# UI.net
KiCad netlist of a schematic drawn in EAGLE
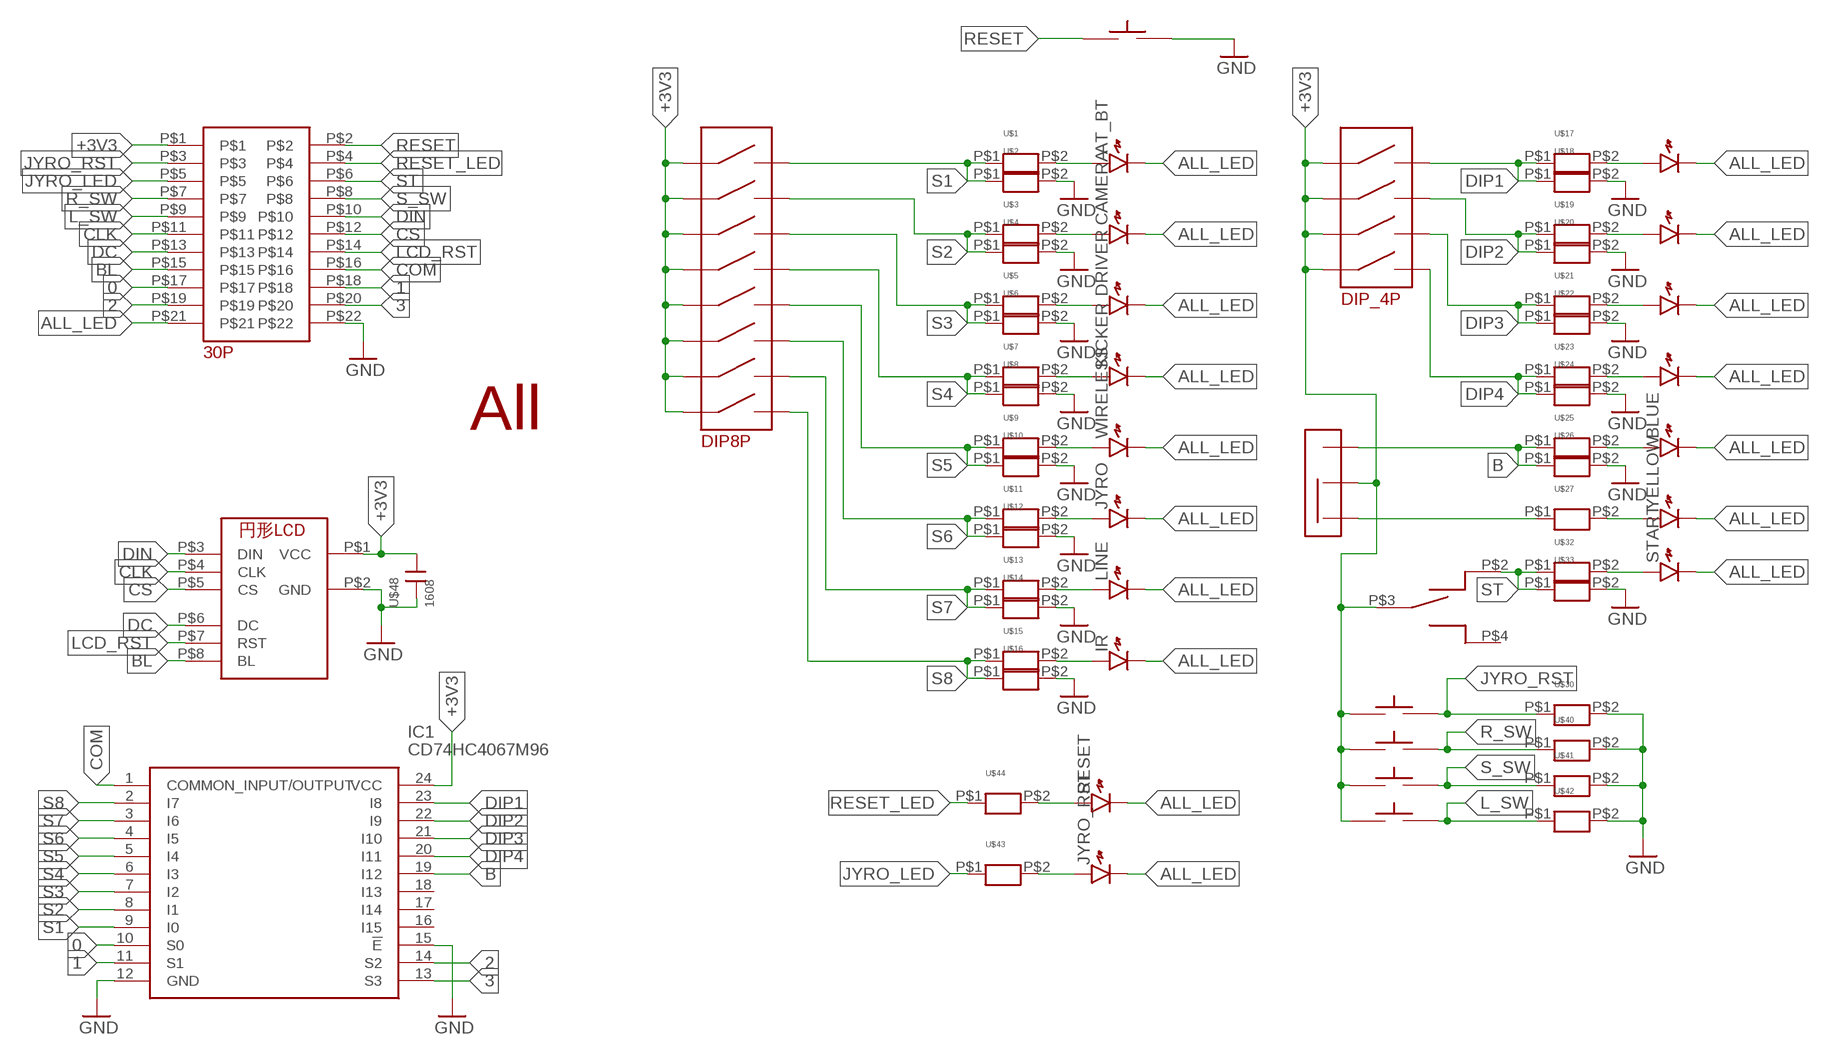
[diagram p0: schematic, sheet 1]
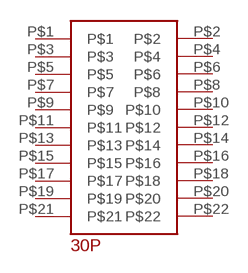
[diagram p1: schematic, sheet 2]

(export (version "E")
  (design (tool "Eeschema 10.0.6"))
  (components
    (comp (ref "AT_BT")
      (value "LED1608")
      (footprint "eagle-import:LED1608")
      (libsource (lib "eagle-import") (part "LED1608"))
    )
    (comp (ref "BLUE")
      (value "LED1608")
      (footprint "eagle-import:LED1608")
      (libsource (lib "eagle-import") (part "LED1608"))
    )
    (comp (ref "CAMERA")
      (value "LED1608")
      (footprint "eagle-import:LED1608")
      (libsource (lib "eagle-import") (part "LED1608"))
    )
    (comp (ref "DRIVER")
      (value "LED1608")
      (footprint "eagle-import:LED1608")
      (libsource (lib "eagle-import") (part "LED1608"))
    )
    (comp (ref "IC1")
      (value "CD74HC4067M96")
      (footprint "eagle-import:SOIC127P1030X265-24N")
      (fields (field (name "MOUSER_PART_NUMBER") "595-CD74HC4067M96"))
      (libsource (lib "eagle-import") (part "CD74HC4067M96"))
    )
    (comp (ref "IR")
      (value "LED1608")
      (footprint "eagle-import:LED1608")
      (libsource (lib "eagle-import") (part "LED1608"))
    )
    (comp (ref "JYRO")
      (value "LED1608")
      (footprint "eagle-import:LED1608")
      (libsource (lib "eagle-import") (part "LED1608"))
    )
    (comp (ref "JYRO_RST")
      (value "LED1608")
      (footprint "eagle-import:LED1608")
      (libsource (lib "eagle-import") (part "LED1608"))
    )
    (comp (ref "KICKER")
      (value "LED1608")
      (footprint "eagle-import:LED1608")
      (libsource (lib "eagle-import") (part "LED1608"))
    )
    (comp (ref "LINE")
      (value "LED1608")
      (footprint "eagle-import:LED1608")
      (libsource (lib "eagle-import") (part "LED1608"))
    )
    (comp (ref "RESET")
      (value "LED1608")
      (footprint "eagle-import:LED1608")
      (libsource (lib "eagle-import") (part "LED1608"))
    )
    (comp (ref "START")
      (value "LED1608")
      (footprint "eagle-import:LED1608")
      (libsource (lib "eagle-import") (part "LED1608"))
    )
    (comp (ref "U$1") (value "R") (footprint "eagle-import:1608") (libsource (lib "eagle-import") (part "R")))
    (comp (ref "U$2") (value "R") (footprint "eagle-import:1608") (libsource (lib "eagle-import") (part "R")))
    (comp (ref "U$3") (value "R") (footprint "eagle-import:1608") (libsource (lib "eagle-import") (part "R")))
    (comp (ref "U$4") (value "R") (footprint "eagle-import:1608") (libsource (lib "eagle-import") (part "R")))
    (comp (ref "U$5") (value "R") (footprint "eagle-import:1608") (libsource (lib "eagle-import") (part "R")))
    (comp (ref "U$6") (value "R") (footprint "eagle-import:1608") (libsource (lib "eagle-import") (part "R")))
    (comp (ref "U$7") (value "R") (footprint "eagle-import:1608") (libsource (lib "eagle-import") (part "R")))
    (comp (ref "U$8") (value "R") (footprint "eagle-import:1608") (libsource (lib "eagle-import") (part "R")))
    (comp (ref "U$9") (value "R") (footprint "eagle-import:1608") (libsource (lib "eagle-import") (part "R")))
    (comp (ref "U$10")
      (value "R")
      (footprint "eagle-import:1608")
      (libsource (lib "eagle-import") (part "R"))
    )
    (comp (ref "U$11")
      (value "R")
      (footprint "eagle-import:1608")
      (libsource (lib "eagle-import") (part "R"))
    )
    (comp (ref "U$12")
      (value "R")
      (footprint "eagle-import:1608")
      (libsource (lib "eagle-import") (part "R"))
    )
    (comp (ref "U$13")
      (value "R")
      (footprint "eagle-import:1608")
      (libsource (lib "eagle-import") (part "R"))
    )
    (comp (ref "U$14")
      (value "R")
      (footprint "eagle-import:1608")
      (libsource (lib "eagle-import") (part "R"))
    )
    (comp (ref "U$15")
      (value "R")
      (footprint "eagle-import:1608")
      (libsource (lib "eagle-import") (part "R"))
    )
    (comp (ref "U$16")
      (value "R")
      (footprint "eagle-import:1608")
      (libsource (lib "eagle-import") (part "R"))
    )
    (comp (ref "U$17")
      (value "R")
      (footprint "eagle-import:1608")
      (libsource (lib "eagle-import") (part "R"))
    )
    (comp (ref "U$18")
      (value "R")
      (footprint "eagle-import:1608")
      (libsource (lib "eagle-import") (part "R"))
    )
    (comp (ref "U$19")
      (value "R")
      (footprint "eagle-import:1608")
      (libsource (lib "eagle-import") (part "R"))
    )
    (comp (ref "U$20")
      (value "R")
      (footprint "eagle-import:1608")
      (libsource (lib "eagle-import") (part "R"))
    )
    (comp (ref "U$21")
      (value "R")
      (footprint "eagle-import:1608")
      (libsource (lib "eagle-import") (part "R"))
    )
    (comp (ref "U$22")
      (value "R")
      (footprint "eagle-import:1608")
      (libsource (lib "eagle-import") (part "R"))
    )
    (comp (ref "U$23")
      (value "R")
      (footprint "eagle-import:1608")
      (libsource (lib "eagle-import") (part "R"))
    )
    (comp (ref "U$24")
      (value "R")
      (footprint "eagle-import:1608")
      (libsource (lib "eagle-import") (part "R"))
    )
    (comp (ref "U$25")
      (value "R")
      (footprint "eagle-import:1608")
      (libsource (lib "eagle-import") (part "R"))
    )
    (comp (ref "U$26")
      (value "R")
      (footprint "eagle-import:1608")
      (libsource (lib "eagle-import") (part "R"))
    )
    (comp (ref "U$27")
      (value "R")
      (footprint "eagle-import:1608")
      (libsource (lib "eagle-import") (part "R"))
    )
    (comp (ref "U$28")
      (value "DIPSW4")
      (footprint "eagle-import:DIPSW4")
      (libsource (lib "eagle-import") (part "DIPSW4"))
    )
    (comp (ref "U$29")
      (value "TAKUTO")
      (footprint "eagle-import:12")
      (libsource (lib "eagle-import") (part "TAKUTO"))
    )
    (comp (ref "U$30")
      (value "R")
      (footprint "eagle-import:1608")
      (libsource (lib "eagle-import") (part "R"))
    )
    (comp (ref "U$31") (value "S") (footprint "eagle-import:S") (libsource (lib "eagle-import") (part "S")))
    (comp (ref "U$32")
      (value "R")
      (footprint "eagle-import:1608")
      (libsource (lib "eagle-import") (part "R"))
    )
    (comp (ref "U$33")
      (value "R")
      (footprint "eagle-import:1608")
      (libsource (lib "eagle-import") (part "R"))
    )
    (comp (ref "U$34")
      (value "TAKUTO")
      (footprint "eagle-import:12")
      (libsource (lib "eagle-import") (part "TAKUTO"))
    )
    (comp (ref "U$35")
      (value "SSW")
      (footprint "eagle-import:SSW")
      (libsource (lib "eagle-import") (part "SSW"))
    )
    (comp (ref "U$36")
      (value "DIPSW8")
      (footprint "eagle-import:DIPSW8")
      (libsource (lib "eagle-import") (part "DIPSW8"))
    )
    (comp (ref "U$37")
      (value "TAKUTO")
      (footprint "eagle-import:12")
      (libsource (lib "eagle-import") (part "TAKUTO"))
    )
    (comp (ref "U$38")
      (value "TAKUTO")
      (footprint "eagle-import:12")
      (libsource (lib "eagle-import") (part "TAKUTO"))
    )
    (comp (ref "U$39")
      (value "TAKUTO")
      (footprint "eagle-import:12")
      (libsource (lib "eagle-import") (part "TAKUTO"))
    )
    (comp (ref "U$40")
      (value "R")
      (footprint "eagle-import:1608")
      (libsource (lib "eagle-import") (part "R"))
    )
    (comp (ref "U$41")
      (value "R")
      (footprint "eagle-import:1608")
      (libsource (lib "eagle-import") (part "R"))
    )
    (comp (ref "U$42")
      (value "R")
      (footprint "eagle-import:1608")
      (libsource (lib "eagle-import") (part "R"))
    )
    (comp (ref "U$43")
      (value "R")
      (footprint "eagle-import:1608")
      (libsource (lib "eagle-import") (part "R"))
    )
    (comp (ref "U$44")
      (value "R")
      (footprint "eagle-import:1608")
      (libsource (lib "eagle-import") (part "R"))
    )
    (comp (ref "U$45")
      (value "LPRP")
      (footprint "eagle-import:LPRO")
      (libsource (lib "eagle-import") (part "LPRP"))
    )
    (comp (ref "U$46")
      (value "LCDEN")
      (footprint "eagle-import:LCD")
      (libsource (lib "eagle-import") (part "LCDEN"))
    )
    (comp (ref "U$48")
      (value "1608")
      (footprint "eagle-import:CON")
      (libsource (lib "eagle-import") (part "1608"))
    )
    (comp (ref "U$49")
      (value "ALL")
      (footprint "eagle-import:ALL")
      (libsource (lib "eagle-import") (part "ALL"))
    )
    (comp (ref "WIRELESS")
      (value "LED1608")
      (footprint "eagle-import:LED1608")
      (libsource (lib "eagle-import") (part "LED1608"))
    )
    (comp (ref "YELLOW")
      (value "LED1608")
      (footprint "eagle-import:LED1608")
      (libsource (lib "eagle-import") (part "LED1608"))
    )
    (comp (ref "Ⅰ")
      (value "LED1608")
      (footprint "eagle-import:LED1608")
      (libsource (lib "eagle-import") (part "LED1608"))
    )
    (comp (ref "Ⅱ")
      (value "LED1608")
      (footprint "eagle-import:LED1608")
      (libsource (lib "eagle-import") (part "LED1608"))
    )
    (comp (ref "Ⅲ")
      (value "LED1608")
      (footprint "eagle-import:LED1608")
      (libsource (lib "eagle-import") (part "LED1608"))
    )
    (comp (ref "Ⅳ")
      (value "LED1608")
      (footprint "eagle-import:LED1608")
      (libsource (lib "eagle-import") (part "LED1608"))
    )
    (comp (ref "U$47")
      (value "LPRP")
      (footprint "eagle-import:LPRO")
      (libsource (lib "eagle-import") (part "LPRP"))
    )
  )
  (nets
    (net (code "1") (name "+3V3") (class "Default")
      (node (ref "IC1") (pin "24") (pinfunction "VCC_24") (pintype "bidirectional"))
      (node (ref "U$28") (pin "P$1") (pinfunction "P$1_P$1") (pintype "bidirectional"))
      (node (ref "U$28") (pin "P$2") (pinfunction "P$2_P$2") (pintype "bidirectional"))
      (node (ref "U$28") (pin "P$3") (pinfunction "P$3_P$3") (pintype "bidirectional"))
      (node (ref "U$28") (pin "P$4") (pinfunction "P$4_P$4") (pintype "bidirectional"))
      (node (ref "U$31") (pin "P$3") (pinfunction "2_P$3") (pintype "bidirectional"))
      (node (ref "U$34") (pin "P$1") (pinfunction "P$1_P$1") (pintype "bidirectional"))
      (node (ref "U$34") (pin "P$2") (pinfunction "P$1_P$2") (pintype "bidirectional"))
      (node (ref "U$35") (pin "P$3") (pinfunction "P$2_P$3") (pintype "bidirectional"))
      (node (ref "U$36") (pin "P$1") (pinfunction "P$1_P$1") (pintype "bidirectional"))
      (node (ref "U$36") (pin "P$2") (pinfunction "P$2_P$2") (pintype "bidirectional"))
      (node (ref "U$36") (pin "P$3") (pinfunction "P$3_P$3") (pintype "bidirectional"))
      (node (ref "U$36") (pin "P$4") (pinfunction "P$4_P$4") (pintype "bidirectional"))
      (node (ref "U$36") (pin "P$5") (pinfunction "P$5_P$5") (pintype "bidirectional"))
      (node (ref "U$36") (pin "P$6") (pinfunction "P$6_P$6") (pintype "bidirectional"))
      (node (ref "U$36") (pin "P$7") (pinfunction "P$7_P$7") (pintype "bidirectional"))
      (node (ref "U$36") (pin "P$8") (pinfunction "P$8_P$8") (pintype "bidirectional"))
      (node (ref "U$37") (pin "P$1") (pinfunction "P$1_P$1") (pintype "bidirectional"))
      (node (ref "U$37") (pin "P$2") (pinfunction "P$1_P$2") (pintype "bidirectional"))
      (node (ref "U$38") (pin "P$1") (pinfunction "P$1_P$1") (pintype "bidirectional"))
      (node (ref "U$38") (pin "P$2") (pinfunction "P$1_P$2") (pintype "bidirectional"))
      (node (ref "U$39") (pin "P$1") (pinfunction "P$1_P$1") (pintype "bidirectional"))
      (node (ref "U$39") (pin "P$2") (pinfunction "P$1_P$2") (pintype "bidirectional"))
      (node (ref "U$45") (pin "P$1") (pinfunction "P$1_P$1") (pintype "bidirectional"))
      (node (ref "U$46") (pin "P$1") (pinfunction "VCC_P$1") (pintype "bidirectional"))
      (node (ref "U$48") (pin "P$1") (pinfunction "1_P$1") (pintype "bidirectional"))
    )
    (net (code "2") (name "0") (class "Default")
      (node (ref "IC1") (pin "10") (pinfunction "S0_10") (pintype "bidirectional"))
      (node (ref "U$45") (pin "P$17") (pinfunction "P$17_P$17") (pintype "bidirectional"))
    )
    (net (code "3") (name "1") (class "Default")
      (node (ref "IC1") (pin "11") (pinfunction "S1_11") (pintype "bidirectional"))
      (node (ref "U$45") (pin "P$18") (pinfunction "P$18_P$18") (pintype "bidirectional"))
    )
    (net (code "4") (name "2") (class "Default")
      (node (ref "IC1") (pin "14") (pinfunction "S2_14") (pintype "bidirectional"))
      (node (ref "U$45") (pin "P$19") (pinfunction "P$19_P$19") (pintype "bidirectional"))
    )
    (net (code "5") (name "3") (class "Default")
      (node (ref "IC1") (pin "13") (pinfunction "S3_13") (pintype "bidirectional"))
      (node (ref "U$45") (pin "P$20") (pinfunction "P$20_P$20") (pintype "bidirectional"))
    )
    (net (code "6") (name "ALL_LED") (class "Default")
      (node (ref "AT_BT") (pin "K") (pinfunction "K_K") (pintype "passive"))
      (node (ref "BLUE") (pin "K") (pinfunction "K_K") (pintype "passive"))
      (node (ref "CAMERA") (pin "K") (pinfunction "K_K") (pintype "passive"))
      (node (ref "DRIVER") (pin "K") (pinfunction "K_K") (pintype "passive"))
      (node (ref "IR") (pin "K") (pinfunction "K_K") (pintype "passive"))
      (node (ref "JYRO") (pin "K") (pinfunction "K_K") (pintype "passive"))
      (node (ref "JYRO_RST") (pin "K") (pinfunction "K_K") (pintype "passive"))
      (node (ref "KICKER") (pin "K") (pinfunction "K_K") (pintype "passive"))
      (node (ref "LINE") (pin "K") (pinfunction "K_K") (pintype "passive"))
      (node (ref "RESET") (pin "K") (pinfunction "K_K") (pintype "passive"))
      (node (ref "START") (pin "K") (pinfunction "K_K") (pintype "passive"))
      (node (ref "U$45") (pin "P$21") (pinfunction "P$21_P$21") (pintype "bidirectional"))
      (node (ref "WIRELESS") (pin "K") (pinfunction "K_K") (pintype "passive"))
      (node (ref "YELLOW") (pin "K") (pinfunction "K_K") (pintype "passive"))
      (node (ref "Ⅰ") (pin "K") (pinfunction "K_K") (pintype "passive"))
      (node (ref "Ⅱ") (pin "K") (pinfunction "K_K") (pintype "passive"))
      (node (ref "Ⅲ") (pin "K") (pinfunction "K_K") (pintype "passive"))
      (node (ref "Ⅳ") (pin "K") (pinfunction "K_K") (pintype "passive"))
    )
    (net (code "7") (name "B") (class "Default")
      (node (ref "IC1") (pin "19") (pinfunction "I12_19") (pintype "bidirectional"))
      (node (ref "U$25") (pin "P$1") (pinfunction "P$1_P$1") (pintype "bidirectional"))
      (node (ref "U$26") (pin "P$1") (pinfunction "P$1_P$1") (pintype "bidirectional"))
      (node (ref "U$35") (pin "P$2") (pinfunction "P$3_P$2") (pintype "bidirectional"))
    )
    (net (code "8") (name "BL") (class "Default")
      (node (ref "U$45") (pin "P$15") (pinfunction "P$15_P$15") (pintype "bidirectional"))
      (node (ref "U$46") (pin "P$8") (pinfunction "BL_P$8") (pintype "bidirectional"))
    )
    (net (code "9") (name "CLK") (class "Default")
      (node (ref "U$45") (pin "P$11") (pinfunction "P$11_P$11") (pintype "bidirectional"))
      (node (ref "U$46") (pin "P$4") (pinfunction "CLK_P$4") (pintype "bidirectional"))
    )
    (net (code "10") (name "COM") (class "Default")
      (node (ref "IC1") (pin "1") (pinfunction "COMMON_INPUT/OUTPUT_1") (pintype "bidirectional"))
      (node (ref "U$45") (pin "P$16") (pinfunction "P$16_P$16") (pintype "bidirectional"))
    )
    (net (code "11") (name "CS") (class "Default")
      (node (ref "U$45") (pin "P$12") (pinfunction "P$12_P$12") (pintype "bidirectional"))
      (node (ref "U$46") (pin "P$5") (pinfunction "CS_P$5") (pintype "bidirectional"))
    )
    (net (code "12") (name "DC") (class "Default")
      (node (ref "U$45") (pin "P$13") (pinfunction "P$13_P$13") (pintype "bidirectional"))
      (node (ref "U$46") (pin "P$6") (pinfunction "DC_P$6") (pintype "bidirectional"))
    )
    (net (code "13") (name "DIN") (class "Default")
      (node (ref "U$45") (pin "P$10") (pinfunction "P$10_P$10") (pintype "bidirectional"))
      (node (ref "U$46") (pin "P$3") (pinfunction "DIN_P$3") (pintype "bidirectional"))
    )
    (net (code "14") (name "DIP1") (class "Default")
      (node (ref "IC1") (pin "23") (pinfunction "I8_23") (pintype "bidirectional"))
      (node (ref "U$17") (pin "P$1") (pinfunction "P$1_P$1") (pintype "bidirectional"))
      (node (ref "U$18") (pin "P$1") (pinfunction "P$1_P$1") (pintype "bidirectional"))
      (node (ref "U$28") (pin "P$8") (pinfunction "P$8_P$8") (pintype "bidirectional"))
    )
    (net (code "15") (name "DIP2") (class "Default")
      (node (ref "IC1") (pin "22") (pinfunction "I9_22") (pintype "bidirectional"))
      (node (ref "U$19") (pin "P$1") (pinfunction "P$1_P$1") (pintype "bidirectional"))
      (node (ref "U$20") (pin "P$1") (pinfunction "P$1_P$1") (pintype "bidirectional"))
      (node (ref "U$28") (pin "P$7") (pinfunction "P$7_P$7") (pintype "bidirectional"))
    )
    (net (code "16") (name "DIP3") (class "Default")
      (node (ref "IC1") (pin "21") (pinfunction "I10_21") (pintype "bidirectional"))
      (node (ref "U$21") (pin "P$1") (pinfunction "P$1_P$1") (pintype "bidirectional"))
      (node (ref "U$22") (pin "P$1") (pinfunction "P$1_P$1") (pintype "bidirectional"))
      (node (ref "U$28") (pin "P$6") (pinfunction "P$6_P$6") (pintype "bidirectional"))
    )
    (net (code "17") (name "DIP4") (class "Default")
      (node (ref "IC1") (pin "20") (pinfunction "I11_20") (pintype "bidirectional"))
      (node (ref "U$23") (pin "P$1") (pinfunction "P$1_P$1") (pintype "bidirectional"))
      (node (ref "U$24") (pin "P$1") (pinfunction "P$1_P$1") (pintype "bidirectional"))
      (node (ref "U$28") (pin "P$5") (pinfunction "P$5_P$5") (pintype "bidirectional"))
    )
    (net (code "18") (name "GND") (class "Default")
      (node (ref "IC1") (pin "12") (pinfunction "GND_12") (pintype "bidirectional"))
      (node (ref "IC1") (pin "15") (pinfunction "~{E}_15") (pintype "bidirectional"))
      (node (ref "U$10") (pin "P$2") (pinfunction "P$2_P$2") (pintype "bidirectional"))
      (node (ref "U$12") (pin "P$2") (pinfunction "P$2_P$2") (pintype "bidirectional"))
      (node (ref "U$14") (pin "P$2") (pinfunction "P$2_P$2") (pintype "bidirectional"))
      (node (ref "U$16") (pin "P$2") (pinfunction "P$2_P$2") (pintype "bidirectional"))
      (node (ref "U$18") (pin "P$2") (pinfunction "P$2_P$2") (pintype "bidirectional"))
      (node (ref "U$2") (pin "P$2") (pinfunction "P$2_P$2") (pintype "bidirectional"))
      (node (ref "U$20") (pin "P$2") (pinfunction "P$2_P$2") (pintype "bidirectional"))
      (node (ref "U$22") (pin "P$2") (pinfunction "P$2_P$2") (pintype "bidirectional"))
      (node (ref "U$24") (pin "P$2") (pinfunction "P$2_P$2") (pintype "bidirectional"))
      (node (ref "U$26") (pin "P$2") (pinfunction "P$2_P$2") (pintype "bidirectional"))
      (node (ref "U$29") (pin "P$3") (pinfunction "P$2_P$3") (pintype "bidirectional"))
      (node (ref "U$29") (pin "P$4") (pinfunction "P$2_P$4") (pintype "bidirectional"))
      (node (ref "U$30") (pin "P$2") (pinfunction "P$2_P$2") (pintype "bidirectional"))
      (node (ref "U$33") (pin "P$2") (pinfunction "P$2_P$2") (pintype "bidirectional"))
      (node (ref "U$4") (pin "P$2") (pinfunction "P$2_P$2") (pintype "bidirectional"))
      (node (ref "U$40") (pin "P$2") (pinfunction "P$2_P$2") (pintype "bidirectional"))
      (node (ref "U$41") (pin "P$2") (pinfunction "P$2_P$2") (pintype "bidirectional"))
      (node (ref "U$42") (pin "P$2") (pinfunction "P$2_P$2") (pintype "bidirectional"))
      (node (ref "U$45") (pin "P$22") (pinfunction "P$22_P$22") (pintype "bidirectional"))
      (node (ref "U$46") (pin "P$2") (pinfunction "GND_P$2") (pintype "bidirectional"))
      (node (ref "U$48") (pin "P$2") (pinfunction "2_P$2") (pintype "bidirectional"))
      (node (ref "U$6") (pin "P$2") (pinfunction "P$2_P$2") (pintype "bidirectional"))
      (node (ref "U$8") (pin "P$2") (pinfunction "P$2_P$2") (pintype "bidirectional"))
    )
    (net (code "19") (name "JYRO_LED") (class "Default")
      (node (ref "U$43") (pin "P$1") (pinfunction "P$1_P$1") (pintype "bidirectional"))
      (node (ref "U$45") (pin "P$5") (pinfunction "P$5_P$5") (pintype "bidirectional"))
    )
    (net (code "20") (name "JYRO_RST") (class "Default")
      (node (ref "U$30") (pin "P$1") (pinfunction "P$1_P$1") (pintype "bidirectional"))
      (node (ref "U$34") (pin "P$3") (pinfunction "P$2_P$3") (pintype "bidirectional"))
      (node (ref "U$34") (pin "P$4") (pinfunction "P$2_P$4") (pintype "bidirectional"))
      (node (ref "U$45") (pin "P$3") (pinfunction "P$3_P$3") (pintype "bidirectional"))
    )
    (net (code "21") (name "LCD_RST") (class "Default")
      (node (ref "U$45") (pin "P$14") (pinfunction "P$14_P$14") (pintype "bidirectional"))
      (node (ref "U$46") (pin "P$7") (pinfunction "RST_P$7") (pintype "bidirectional"))
    )
    (net (code "22") (name "L_SW") (class "Default")
      (node (ref "U$39") (pin "P$3") (pinfunction "P$2_P$3") (pintype "bidirectional"))
      (node (ref "U$39") (pin "P$4") (pinfunction "P$2_P$4") (pintype "bidirectional"))
      (node (ref "U$42") (pin "P$1") (pinfunction "P$1_P$1") (pintype "bidirectional"))
      (node (ref "U$45") (pin "P$9") (pinfunction "P$9_P$9") (pintype "bidirectional"))
    )
    (net (code "23") (name "Net-(AT_BT-PadA)") (class "Default")
      (node (ref "AT_BT") (pin "A") (pinfunction "A_A") (pintype "passive"))
      (node (ref "U$1") (pin "P$2") (pinfunction "P$2_P$2") (pintype "bidirectional"))
    )
    (net (code "24") (name "Net-(BLUE-PadA)") (class "Default")
      (node (ref "BLUE") (pin "A") (pinfunction "A_A") (pintype "passive"))
      (node (ref "U$25") (pin "P$2") (pinfunction "P$2_P$2") (pintype "bidirectional"))
    )
    (net (code "25") (name "Net-(CAMERA-PadA)") (class "Default")
      (node (ref "CAMERA") (pin "A") (pinfunction "A_A") (pintype "passive"))
      (node (ref "U$3") (pin "P$2") (pinfunction "P$2_P$2") (pintype "bidirectional"))
    )
    (net (code "26") (name "Net-(DRIVER-PadA)") (class "Default")
      (node (ref "DRIVER") (pin "A") (pinfunction "A_A") (pintype "passive"))
      (node (ref "U$5") (pin "P$2") (pinfunction "P$2_P$2") (pintype "bidirectional"))
    )
    (net (code "27") (name "Net-(IR-PadA)") (class "Default")
      (node (ref "IR") (pin "A") (pinfunction "A_A") (pintype "passive"))
      (node (ref "U$15") (pin "P$2") (pinfunction "P$2_P$2") (pintype "bidirectional"))
    )
    (net (code "28") (name "Net-(JYRO-PadA)") (class "Default")
      (node (ref "JYRO") (pin "A") (pinfunction "A_A") (pintype "passive"))
      (node (ref "U$11") (pin "P$2") (pinfunction "P$2_P$2") (pintype "bidirectional"))
    )
    (net (code "29") (name "Net-(JYRO_RST-PadA)") (class "Default")
      (node (ref "JYRO_RST") (pin "A") (pinfunction "A_A") (pintype "passive"))
      (node (ref "U$43") (pin "P$2") (pinfunction "P$2_P$2") (pintype "bidirectional"))
    )
    (net (code "30") (name "Net-(KICKER-PadA)") (class "Default")
      (node (ref "KICKER") (pin "A") (pinfunction "A_A") (pintype "passive"))
      (node (ref "U$7") (pin "P$2") (pinfunction "P$2_P$2") (pintype "bidirectional"))
    )
    (net (code "31") (name "Net-(LINE-PadA)") (class "Default")
      (node (ref "LINE") (pin "A") (pinfunction "A_A") (pintype "passive"))
      (node (ref "U$13") (pin "P$2") (pinfunction "P$2_P$2") (pintype "bidirectional"))
    )
    (net (code "32") (name "Net-(RESET-PadA)") (class "Default")
      (node (ref "RESET") (pin "A") (pinfunction "A_A") (pintype "passive"))
      (node (ref "U$44") (pin "P$2") (pinfunction "P$2_P$2") (pintype "bidirectional"))
    )
    (net (code "33") (name "Net-(START-PadA)") (class "Default")
      (node (ref "START") (pin "A") (pinfunction "A_A") (pintype "passive"))
      (node (ref "U$32") (pin "P$2") (pinfunction "P$2_P$2") (pintype "bidirectional"))
    )
    (net (code "34") (name "Net-(U$9-PadP$2)") (class "Default")
      (node (ref "U$9") (pin "P$2") (pinfunction "P$2_P$2") (pintype "bidirectional"))
      (node (ref "WIRELESS") (pin "A") (pinfunction "A_A") (pintype "passive"))
    )
    (net (code "35") (name "Net-(U$17-PadP$2)") (class "Default")
      (node (ref "U$17") (pin "P$2") (pinfunction "P$2_P$2") (pintype "bidirectional"))
      (node (ref "Ⅰ") (pin "A") (pinfunction "A_A") (pintype "passive"))
    )
    (net (code "36") (name "Net-(U$19-PadP$2)") (class "Default")
      (node (ref "U$19") (pin "P$2") (pinfunction "P$2_P$2") (pintype "bidirectional"))
      (node (ref "Ⅱ") (pin "A") (pinfunction "A_A") (pintype "passive"))
    )
    (net (code "37") (name "Net-(U$21-PadP$2)") (class "Default")
      (node (ref "U$21") (pin "P$2") (pinfunction "P$2_P$2") (pintype "bidirectional"))
      (node (ref "Ⅲ") (pin "A") (pinfunction "A_A") (pintype "passive"))
    )
    (net (code "38") (name "Net-(U$23-PadP$2)") (class "Default")
      (node (ref "U$23") (pin "P$2") (pinfunction "P$2_P$2") (pintype "bidirectional"))
      (node (ref "Ⅳ") (pin "A") (pinfunction "A_A") (pintype "passive"))
    )
    (net (code "39") (name "Net-(U$27-PadP$1)") (class "Default")
      (node (ref "U$27") (pin "P$1") (pinfunction "P$1_P$1") (pintype "bidirectional"))
      (node (ref "U$35") (pin "P$1") (pinfunction "P$1_P$1") (pintype "bidirectional"))
    )
    (net (code "40") (name "Net-(U$27-PadP$2)") (class "Default")
      (node (ref "U$27") (pin "P$2") (pinfunction "P$2_P$2") (pintype "bidirectional"))
      (node (ref "YELLOW") (pin "A") (pinfunction "A_A") (pintype "passive"))
    )
    (net (code "41") (name "RESET") (class "Default")
      (node (ref "U$29") (pin "P$1") (pinfunction "P$1_P$1") (pintype "bidirectional"))
      (node (ref "U$29") (pin "P$2") (pinfunction "P$1_P$2") (pintype "bidirectional"))
      (node (ref "U$45") (pin "P$2") (pinfunction "P$2_P$2") (pintype "bidirectional"))
    )
    (net (code "42") (name "RESET_LED") (class "Default")
      (node (ref "U$44") (pin "P$1") (pinfunction "P$1_P$1") (pintype "bidirectional"))
      (node (ref "U$45") (pin "P$4") (pinfunction "P$4_P$4") (pintype "bidirectional"))
    )
    (net (code "43") (name "R_SW") (class "Default")
      (node (ref "U$37") (pin "P$3") (pinfunction "P$2_P$3") (pintype "bidirectional"))
      (node (ref "U$37") (pin "P$4") (pinfunction "P$2_P$4") (pintype "bidirectional"))
      (node (ref "U$40") (pin "P$1") (pinfunction "P$1_P$1") (pintype "bidirectional"))
      (node (ref "U$45") (pin "P$7") (pinfunction "P$7_P$7") (pintype "bidirectional"))
    )
    (net (code "44") (name "S1") (class "Default")
      (node (ref "IC1") (pin "9") (pinfunction "I0_9") (pintype "bidirectional"))
      (node (ref "U$1") (pin "P$1") (pinfunction "P$1_P$1") (pintype "bidirectional"))
      (node (ref "U$2") (pin "P$1") (pinfunction "P$1_P$1") (pintype "bidirectional"))
      (node (ref "U$36") (pin "P$16") (pinfunction "P$16_P$16") (pintype "bidirectional"))
    )
    (net (code "45") (name "S2") (class "Default")
      (node (ref "IC1") (pin "8") (pinfunction "I1_8") (pintype "bidirectional"))
      (node (ref "U$3") (pin "P$1") (pinfunction "P$1_P$1") (pintype "bidirectional"))
      (node (ref "U$36") (pin "P$15") (pinfunction "P$15_P$15") (pintype "bidirectional"))
      (node (ref "U$4") (pin "P$1") (pinfunction "P$1_P$1") (pintype "bidirectional"))
    )
    (net (code "46") (name "S3") (class "Default")
      (node (ref "IC1") (pin "7") (pinfunction "I2_7") (pintype "bidirectional"))
      (node (ref "U$36") (pin "P$14") (pinfunction "P$14_P$14") (pintype "bidirectional"))
      (node (ref "U$5") (pin "P$1") (pinfunction "P$1_P$1") (pintype "bidirectional"))
      (node (ref "U$6") (pin "P$1") (pinfunction "P$1_P$1") (pintype "bidirectional"))
    )
    (net (code "47") (name "S4") (class "Default")
      (node (ref "IC1") (pin "6") (pinfunction "I3_6") (pintype "bidirectional"))
      (node (ref "U$36") (pin "P$13") (pinfunction "P$13_P$13") (pintype "bidirectional"))
      (node (ref "U$7") (pin "P$1") (pinfunction "P$1_P$1") (pintype "bidirectional"))
      (node (ref "U$8") (pin "P$1") (pinfunction "P$1_P$1") (pintype "bidirectional"))
    )
    (net (code "48") (name "S5") (class "Default")
      (node (ref "IC1") (pin "5") (pinfunction "I4_5") (pintype "bidirectional"))
      (node (ref "U$10") (pin "P$1") (pinfunction "P$1_P$1") (pintype "bidirectional"))
      (node (ref "U$36") (pin "P$12") (pinfunction "P$12_P$12") (pintype "bidirectional"))
      (node (ref "U$9") (pin "P$1") (pinfunction "P$1_P$1") (pintype "bidirectional"))
    )
    (net (code "49") (name "S6") (class "Default")
      (node (ref "IC1") (pin "4") (pinfunction "I5_4") (pintype "bidirectional"))
      (node (ref "U$11") (pin "P$1") (pinfunction "P$1_P$1") (pintype "bidirectional"))
      (node (ref "U$12") (pin "P$1") (pinfunction "P$1_P$1") (pintype "bidirectional"))
      (node (ref "U$36") (pin "P$11") (pinfunction "P$11_P$11") (pintype "bidirectional"))
    )
    (net (code "50") (name "S7") (class "Default")
      (node (ref "IC1") (pin "3") (pinfunction "I6_3") (pintype "bidirectional"))
      (node (ref "U$13") (pin "P$1") (pinfunction "P$1_P$1") (pintype "bidirectional"))
      (node (ref "U$14") (pin "P$1") (pinfunction "P$1_P$1") (pintype "bidirectional"))
      (node (ref "U$36") (pin "P$10") (pinfunction "P$10_P$10") (pintype "bidirectional"))
    )
    (net (code "51") (name "S8") (class "Default")
      (node (ref "IC1") (pin "2") (pinfunction "I7_2") (pintype "bidirectional"))
      (node (ref "U$15") (pin "P$1") (pinfunction "P$1_P$1") (pintype "bidirectional"))
      (node (ref "U$16") (pin "P$1") (pinfunction "P$1_P$1") (pintype "bidirectional"))
      (node (ref "U$36") (pin "P$9") (pinfunction "P$9_P$9") (pintype "bidirectional"))
    )
    (net (code "52") (name "ST") (class "Default")
      (node (ref "U$31") (pin "P$2") (pinfunction "1_P$2") (pintype "bidirectional"))
      (node (ref "U$32") (pin "P$1") (pinfunction "P$1_P$1") (pintype "bidirectional"))
      (node (ref "U$33") (pin "P$1") (pinfunction "P$1_P$1") (pintype "bidirectional"))
      (node (ref "U$45") (pin "P$6") (pinfunction "P$6_P$6") (pintype "bidirectional"))
    )
    (net (code "53") (name "S_SW") (class "Default")
      (node (ref "U$38") (pin "P$3") (pinfunction "P$2_P$3") (pintype "bidirectional"))
      (node (ref "U$38") (pin "P$4") (pinfunction "P$2_P$4") (pintype "bidirectional"))
      (node (ref "U$41") (pin "P$1") (pinfunction "P$1_P$1") (pintype "bidirectional"))
      (node (ref "U$45") (pin "P$8") (pinfunction "P$8_P$8") (pintype "bidirectional"))
    )
    (net (code "54") (name "unconnected-(IC1-I13-Pad18)") (class "Default")
      (node (ref "IC1") (pin "18") (pinfunction "I13_18") (pintype "bidirectional"))
    )
    (net (code "55") (name "unconnected-(IC1-I14-Pad17)") (class "Default")
      (node (ref "IC1") (pin "17") (pinfunction "I14_17") (pintype "bidirectional"))
    )
    (net (code "56") (name "unconnected-(IC1-I15-Pad16)") (class "Default")
      (node (ref "IC1") (pin "16") (pinfunction "I15_16") (pintype "bidirectional"))
    )
    (net (code "57") (name "unconnected-(U$31-3-PadP$4)") (class "Default")
      (node (ref "U$31") (pin "P$4") (pinfunction "3_P$4") (pintype "bidirectional"))
    )
    (net (code "58") (name "unconnected-(U$47-PadP$1)") (class "Default")
      (node (ref "U$47") (pin "P$1") (pinfunction "P$1_P$1") (pintype "bidirectional"))
    )
    (net (code "59") (name "unconnected-(U$47-PadP$2)") (class "Default")
      (node (ref "U$47") (pin "P$2") (pinfunction "P$2_P$2") (pintype "bidirectional"))
    )
    (net (code "60") (name "unconnected-(U$47-PadP$3)") (class "Default")
      (node (ref "U$47") (pin "P$3") (pinfunction "P$3_P$3") (pintype "bidirectional"))
    )
    (net (code "61") (name "unconnected-(U$47-PadP$4)") (class "Default")
      (node (ref "U$47") (pin "P$4") (pinfunction "P$4_P$4") (pintype "bidirectional"))
    )
    (net (code "62") (name "unconnected-(U$47-PadP$5)") (class "Default")
      (node (ref "U$47") (pin "P$5") (pinfunction "P$5_P$5") (pintype "bidirectional"))
    )
    (net (code "63") (name "unconnected-(U$47-PadP$6)") (class "Default")
      (node (ref "U$47") (pin "P$6") (pinfunction "P$6_P$6") (pintype "bidirectional"))
    )
    (net (code "64") (name "unconnected-(U$47-PadP$7)") (class "Default")
      (node (ref "U$47") (pin "P$7") (pinfunction "P$7_P$7") (pintype "bidirectional"))
    )
    (net (code "65") (name "unconnected-(U$47-PadP$8)") (class "Default")
      (node (ref "U$47") (pin "P$8") (pinfunction "P$8_P$8") (pintype "bidirectional"))
    )
    (net (code "66") (name "unconnected-(U$47-PadP$9)") (class "Default")
      (node (ref "U$47") (pin "P$9") (pinfunction "P$9_P$9") (pintype "bidirectional"))
    )
    (net (code "67") (name "unconnected-(U$47-PadP$10)") (class "Default")
      (node (ref "U$47") (pin "P$10") (pinfunction "P$10_P$10") (pintype "bidirectional"))
    )
    (net (code "68") (name "unconnected-(U$47-PadP$11)") (class "Default")
      (node (ref "U$47") (pin "P$11") (pinfunction "P$11_P$11") (pintype "bidirectional"))
    )
    (net (code "69") (name "unconnected-(U$47-PadP$12)") (class "Default")
      (node (ref "U$47") (pin "P$12") (pinfunction "P$12_P$12") (pintype "bidirectional"))
    )
    (net (code "70") (name "unconnected-(U$47-PadP$13)") (class "Default")
      (node (ref "U$47") (pin "P$13") (pinfunction "P$13_P$13") (pintype "bidirectional"))
    )
    (net (code "71") (name "unconnected-(U$47-PadP$14)") (class "Default")
      (node (ref "U$47") (pin "P$14") (pinfunction "P$14_P$14") (pintype "bidirectional"))
    )
    (net (code "72") (name "unconnected-(U$47-PadP$15)") (class "Default")
      (node (ref "U$47") (pin "P$15") (pinfunction "P$15_P$15") (pintype "bidirectional"))
    )
    (net (code "73") (name "unconnected-(U$47-PadP$16)") (class "Default")
      (node (ref "U$47") (pin "P$16") (pinfunction "P$16_P$16") (pintype "bidirectional"))
    )
    (net (code "74") (name "unconnected-(U$47-PadP$17)") (class "Default")
      (node (ref "U$47") (pin "P$17") (pinfunction "P$17_P$17") (pintype "bidirectional"))
    )
    (net (code "75") (name "unconnected-(U$47-PadP$18)") (class "Default")
      (node (ref "U$47") (pin "P$18") (pinfunction "P$18_P$18") (pintype "bidirectional"))
    )
    (net (code "76") (name "unconnected-(U$47-PadP$19)") (class "Default")
      (node (ref "U$47") (pin "P$19") (pinfunction "P$19_P$19") (pintype "bidirectional"))
    )
    (net (code "77") (name "unconnected-(U$47-PadP$20)") (class "Default")
      (node (ref "U$47") (pin "P$20") (pinfunction "P$20_P$20") (pintype "bidirectional"))
    )
    (net (code "78") (name "unconnected-(U$47-PadP$21)") (class "Default")
      (node (ref "U$47") (pin "P$21") (pinfunction "P$21_P$21") (pintype "bidirectional"))
    )
    (net (code "79") (name "unconnected-(U$47-PadP$22)") (class "Default")
      (node (ref "U$47") (pin "P$22") (pinfunction "P$22_P$22") (pintype "bidirectional"))
    )
  )
)
